# CAN-INTERFACES.net
KiCad netlist of a schematic drawn in Altium Designer
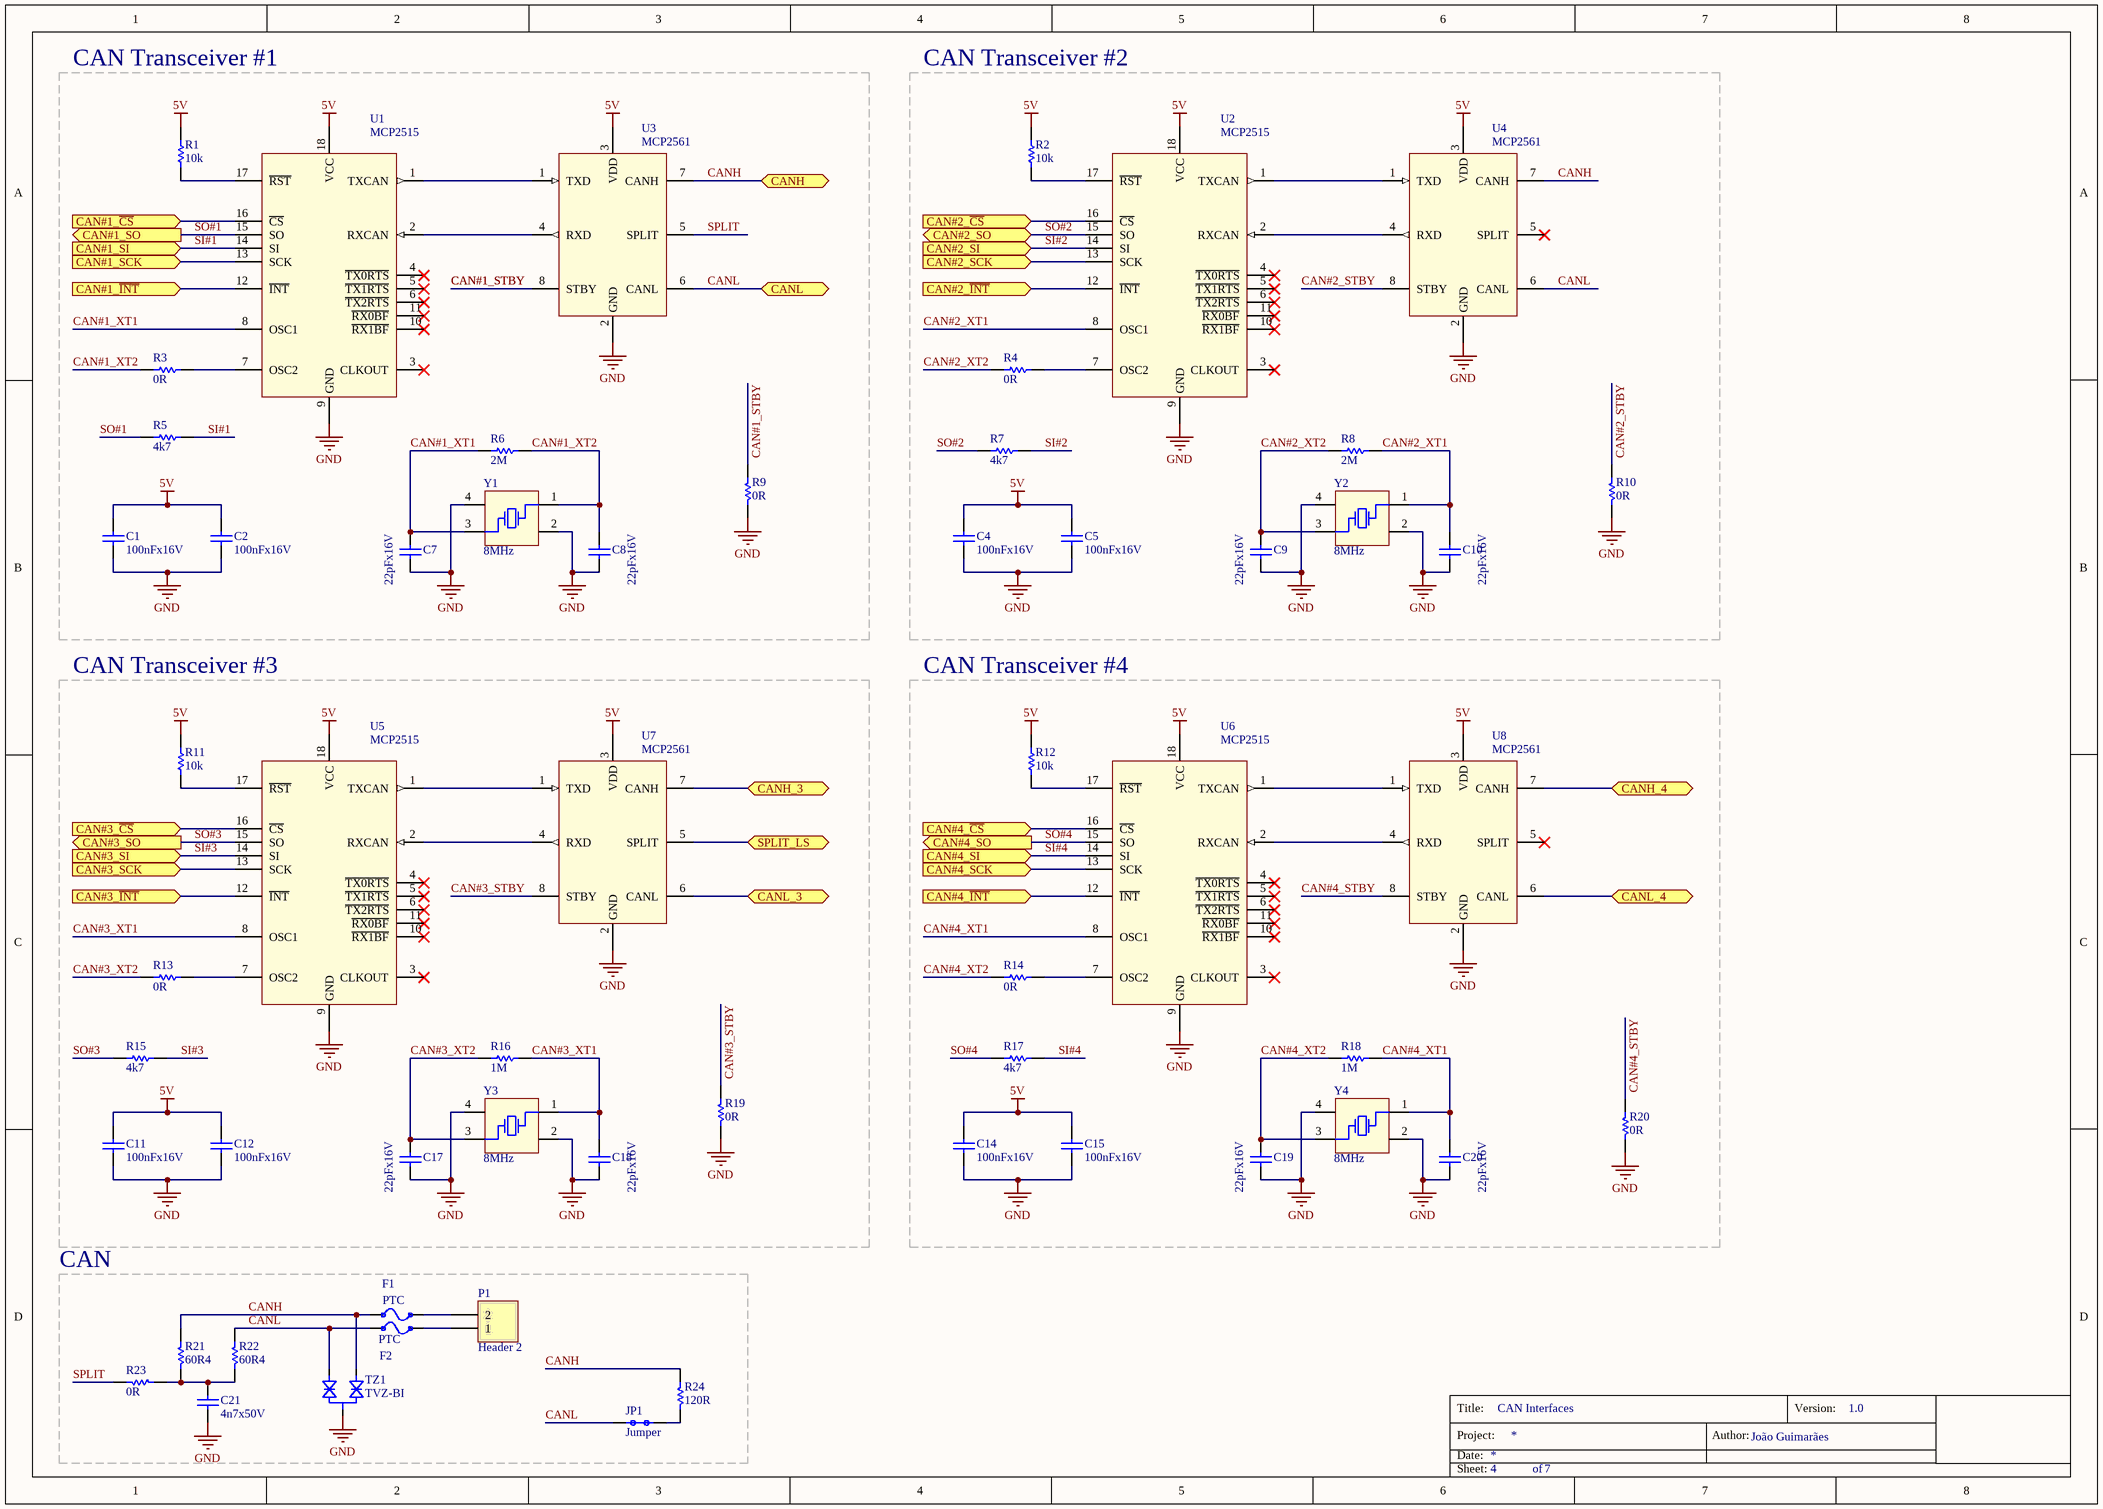
[diagram p0: CAN-INTERFACES.SchDoc]

(export (version "E")
  (design (tool "Eeschema 10.0.6"))
  (components
    (comp (ref "C1")
      (value "100nFx16V")
      (footprint "DISC-0603")
      (description "Capacitor")
      (libsource (lib "IntLib") (part "Cap"))
    )
    (comp (ref "C2")
      (value "100nFx16V")
      (footprint "DISC-0603")
      (description "Capacitor")
      (libsource (lib "IntLib") (part "Cap"))
    )
    (comp (ref "C4")
      (value "100nFx16V")
      (footprint "DISC-0603")
      (description "Capacitor")
      (libsource (lib "IntLib") (part "Cap"))
    )
    (comp (ref "C5")
      (value "100nFx16V")
      (footprint "DISC-0603")
      (description "Capacitor")
      (libsource (lib "IntLib") (part "Cap"))
    )
    (comp (ref "C7")
      (value "22pFx16V")
      (footprint "DISC-0603")
      (description "Capacitor")
      (libsource (lib "IntLib") (part "Cap"))
    )
    (comp (ref "C8")
      (value "22pFx16V")
      (footprint "DISC-0603")
      (description "Capacitor")
      (libsource (lib "IntLib") (part "Cap"))
    )
    (comp (ref "C9")
      (value "22pFx16V")
      (footprint "DISC-0603")
      (description "Capacitor")
      (libsource (lib "IntLib") (part "Cap"))
    )
    (comp (ref "C10")
      (value "22pFx16V")
      (footprint "DISC-0603")
      (description "Capacitor")
      (libsource (lib "IntLib") (part "Cap"))
    )
    (comp (ref "C11")
      (value "100nFx16V")
      (footprint "DISC-0603")
      (description "Capacitor")
      (libsource (lib "IntLib") (part "Cap"))
    )
    (comp (ref "C12")
      (value "100nFx16V")
      (footprint "DISC-0603")
      (description "Capacitor")
      (libsource (lib "IntLib") (part "Cap"))
    )
    (comp (ref "C14")
      (value "100nFx16V")
      (footprint "DISC-0603")
      (description "Capacitor")
      (libsource (lib "IntLib") (part "Cap"))
    )
    (comp (ref "C15")
      (value "100nFx16V")
      (footprint "DISC-0603")
      (description "Capacitor")
      (libsource (lib "IntLib") (part "Cap"))
    )
    (comp (ref "C17")
      (value "22pFx16V")
      (footprint "DISC-0603")
      (description "Capacitor")
      (libsource (lib "IntLib") (part "Cap"))
    )
    (comp (ref "C18")
      (value "22pFx16V")
      (footprint "DISC-0603")
      (description "Capacitor")
      (libsource (lib "IntLib") (part "Cap"))
    )
    (comp (ref "C19")
      (value "22pFx16V")
      (footprint "DISC-0603")
      (description "Capacitor")
      (libsource (lib "IntLib") (part "Cap"))
    )
    (comp (ref "C20")
      (value "22pFx16V")
      (footprint "DISC-0603")
      (description "Capacitor")
      (libsource (lib "IntLib") (part "Cap"))
    )
    (comp (ref "C21")
      (value "4n7x50V")
      (footprint "DISC-0603")
      (description "Capacitor")
      (libsource (lib "IntLib") (part "Cap"))
    )
    (comp (ref "F1")
      (value "PTC")
      (footprint "DISC-FUSE-1206")
      (description "Fuse")
      (fields (field (name "PUBLISHER") "Altium Limited"))
      (libsource (lib "IntLib") (part "Fuse 2"))
    )
    (comp (ref "F2")
      (value "PTC")
      (footprint "DISC-FUSE-1206")
      (description "Fuse")
      (fields (field (name "PUBLISHER") "Altium Limited"))
      (libsource (lib "IntLib") (part "Fuse 2"))
    )
    (comp (ref "JP1")
      (value "Jumper")
      (footprint "CON-HEADER-1X2-PTH")
      (description "Resistor")
      (libsource (lib "IntLib") (part "Jumper"))
    )
    (comp (ref "P1")
      (value "Header 2")
      (footprint "CON-BORNE-2")
      (description "Header, 2-Pin")
      (fields (field (name "PUBLISHER") "Altium Limited"))
      (libsource (lib "IntLib") (part "Header 2"))
    )
    (comp (ref "R1")
      (value "10k")
      (footprint "DISC-0603")
      (description "Resistor")
      (libsource (lib "IntLib") (part "Res"))
    )
    (comp (ref "R2")
      (value "10k")
      (footprint "DISC-0603")
      (description "Resistor")
      (libsource (lib "IntLib") (part "Res"))
    )
    (comp (ref "R3")
      (value "0R")
      (footprint "DISC-0603")
      (description "Resistor")
      (libsource (lib "IntLib") (part "Res"))
    )
    (comp (ref "R4")
      (value "0R")
      (footprint "DISC-0603")
      (description "Resistor")
      (libsource (lib "IntLib") (part "Res"))
    )
    (comp (ref "R5")
      (value "4k7")
      (footprint "DISC-0603")
      (description "Resistor")
      (libsource (lib "IntLib") (part "Res"))
    )
    (comp (ref "R6")
      (value "2M")
      (footprint "DISC-0603")
      (description "Resistor")
      (libsource (lib "IntLib") (part "Res"))
    )
    (comp (ref "R7")
      (value "4k7")
      (footprint "DISC-0603")
      (description "Resistor")
      (libsource (lib "IntLib") (part "Res"))
    )
    (comp (ref "R8")
      (value "2M")
      (footprint "DISC-0603")
      (description "Resistor")
      (libsource (lib "IntLib") (part "Res"))
    )
    (comp (ref "R9")
      (value "0R")
      (footprint "DISC-0603")
      (description "Resistor")
      (libsource (lib "IntLib") (part "Res"))
    )
    (comp (ref "R10")
      (value "0R")
      (footprint "DISC-0603")
      (description "Resistor")
      (libsource (lib "IntLib") (part "Res"))
    )
    (comp (ref "R11")
      (value "10k")
      (footprint "DISC-0603")
      (description "Resistor")
      (libsource (lib "IntLib") (part "Res"))
    )
    (comp (ref "R12")
      (value "10k")
      (footprint "DISC-0603")
      (description "Resistor")
      (libsource (lib "IntLib") (part "Res"))
    )
    (comp (ref "R13")
      (value "0R")
      (footprint "DISC-0603")
      (description "Resistor")
      (libsource (lib "IntLib") (part "Res"))
    )
    (comp (ref "R14")
      (value "0R")
      (footprint "DISC-0603")
      (description "Resistor")
      (libsource (lib "IntLib") (part "Res"))
    )
    (comp (ref "R15")
      (value "4k7")
      (footprint "DISC-0603")
      (description "Resistor")
      (libsource (lib "IntLib") (part "Res"))
    )
    (comp (ref "R16")
      (value "1M")
      (footprint "DISC-0603")
      (description "Resistor")
      (libsource (lib "IntLib") (part "Res"))
    )
    (comp (ref "R17")
      (value "4k7")
      (footprint "DISC-0603")
      (description "Resistor")
      (libsource (lib "IntLib") (part "Res"))
    )
    (comp (ref "R18")
      (value "1M")
      (footprint "DISC-0603")
      (description "Resistor")
      (libsource (lib "IntLib") (part "Res"))
    )
    (comp (ref "R19")
      (value "0R")
      (footprint "DISC-0603")
      (description "Resistor")
      (libsource (lib "IntLib") (part "Res"))
    )
    (comp (ref "R20")
      (value "0R")
      (footprint "DISC-0603")
      (description "Resistor")
      (libsource (lib "IntLib") (part "Res"))
    )
    (comp (ref "R21") (value "60R4") (footprint "DISC-0805") (libsource (lib "IntLib") (part "Res")))
    (comp (ref "R22") (value "60R4") (footprint "DISC-0805") (libsource (lib "IntLib") (part "Res")))
    (comp (ref "R23")
      (value "0R")
      (footprint "DISC-0603")
      (description "Resistor")
      (libsource (lib "IntLib") (part "Res"))
    )
    (comp (ref "R24")
      (value "120R")
      (footprint "DISC-0805")
      (description "60R4")
      (libsource (lib "IntLib") (part "Res"))
    )
    (comp (ref "TZ1")
      (value "TVZ-BI")
      (footprint "DISC-SOT-23")
      (description "TVZ-Bi-Directional")
      (libsource (lib "IntLib") (part "TVZ-Bi-Dual"))
    )
    (comp (ref "U1")
      (value "MCP2515")
      (footprint "CI-SOICW-18")
      (description "Stand-Alone CAN Controller With SPI Interface")
      (libsource (lib "IntLib") (part "MCP2515"))
    )
    (comp (ref "U2")
      (value "MCP2515")
      (footprint "CI-SOICW-18")
      (description "Stand-Alone CAN Controller With SPI Interface")
      (libsource (lib "IntLib") (part "MCP2515"))
    )
    (comp (ref "U3")
      (value "MCP2561")
      (footprint "CI-SOIC-8")
      (description "High speed CAN transceiver")
      (libsource (lib "IntLib") (part "MCP2561"))
    )
    (comp (ref "U4")
      (value "MCP2561")
      (footprint "CI-SOIC-8")
      (description "High speed CAN transceiver")
      (libsource (lib "IntLib") (part "MCP2561"))
    )
    (comp (ref "U5")
      (value "MCP2515")
      (footprint "CI-SOICW-18")
      (description "Stand-Alone CAN Controller With SPI Interface")
      (libsource (lib "IntLib") (part "MCP2515"))
    )
    (comp (ref "U6")
      (value "MCP2515")
      (footprint "CI-SOICW-18")
      (description "Stand-Alone CAN Controller With SPI Interface")
      (libsource (lib "IntLib") (part "MCP2515"))
    )
    (comp (ref "U7")
      (value "MCP2561")
      (footprint "CI-SOIC-8")
      (description "High speed CAN transceiver")
      (libsource (lib "IntLib") (part "MCP2561"))
    )
    (comp (ref "U8")
      (value "MCP2561")
      (footprint "CI-SOIC-8")
      (description "High speed CAN transceiver")
      (libsource (lib "IntLib") (part "MCP2561"))
    )
    (comp (ref "Y1")
      (value "8MHz")
      (footprint "DISC-CRYSTAL-4P-3.2X2.5")
      (description "XTAL-4-PIN")
      (libsource (lib "IntLib") (part "XTAL-4-PIN"))
    )
    (comp (ref "Y2")
      (value "8MHz")
      (footprint "DISC-CRYSTAL-4P-3.2X2.5")
      (description "XTAL-4-PIN")
      (libsource (lib "IntLib") (part "XTAL-4-PIN"))
    )
    (comp (ref "Y3")
      (value "8MHz")
      (footprint "DISC-CRYSTAL-4P-3.2X2.5")
      (description "XTAL-4-PIN")
      (libsource (lib "IntLib") (part "XTAL-4-PIN"))
    )
    (comp (ref "Y4")
      (value "8MHz")
      (footprint "DISC-CRYSTAL-4P-3.2X2.5")
      (description "XTAL-4-PIN")
      (libsource (lib "IntLib") (part "XTAL-4-PIN"))
    )
  )
  (nets
    (net (code "1") (name "/CAN#1_SCK") (class "Default")
      (node (ref "U1") (pin "13") (pinfunction "SCK_13") (pintype "passive"))
    )
    (net (code "2") (name "/CAN#1_STBY") (class "Default")
      (node (ref "R9") (pin "2") (pinfunction "2_2") (pintype "passive"))
      (node (ref "U3") (pin "8") (pinfunction "STBY_8") (pintype "passive"))
    )
    (net (code "3") (name "/CAN#1_XT1") (class "Default")
      (node (ref "C7") (pin "2") (pinfunction "2_2") (pintype "passive"))
      (node (ref "R6") (pin "1") (pinfunction "1_1") (pintype "passive"))
      (node (ref "U1") (pin "8") (pinfunction "OSC1_8") (pintype "passive"))
      (node (ref "Y1") (pin "3") (pinfunction "OSC2_3") (pintype "passive"))
    )
    (net (code "4") (name "/CAN#1_XT2") (class "Default")
      (node (ref "C8") (pin "2") (pinfunction "2_2") (pintype "passive"))
      (node (ref "R3") (pin "2") (pinfunction "2_2") (pintype "passive"))
      (node (ref "R6") (pin "2") (pinfunction "2_2") (pintype "passive"))
      (node (ref "Y1") (pin "1") (pinfunction "OSC1_1") (pintype "passive"))
    )
    (net (code "5") (name "/CAN#1_~{CS}") (class "Default")
      (node (ref "U1") (pin "16") (pinfunction "~{CS}_16") (pintype "passive"))
    )
    (net (code "6") (name "/CAN#1_~{INT}") (class "Default")
      (node (ref "U1") (pin "12") (pinfunction "~{INT}_12") (pintype "passive"))
    )
    (net (code "7") (name "/CAN#2_SCK") (class "Default")
      (node (ref "U2") (pin "13") (pinfunction "SCK_13") (pintype "passive"))
    )
    (net (code "8") (name "/CAN#2_STBY") (class "Default")
      (node (ref "R10") (pin "2") (pinfunction "2_2") (pintype "passive"))
      (node (ref "U4") (pin "8") (pinfunction "STBY_8") (pintype "passive"))
    )
    (net (code "9") (name "/CAN#2_XT1") (class "Default")
      (node (ref "C10") (pin "2") (pinfunction "2_2") (pintype "passive"))
      (node (ref "R8") (pin "2") (pinfunction "2_2") (pintype "passive"))
      (node (ref "U2") (pin "8") (pinfunction "OSC1_8") (pintype "passive"))
      (node (ref "Y2") (pin "1") (pinfunction "OSC1_1") (pintype "passive"))
    )
    (net (code "10") (name "/CAN#2_XT2") (class "Default")
      (node (ref "C9") (pin "2") (pinfunction "2_2") (pintype "passive"))
      (node (ref "R4") (pin "2") (pinfunction "2_2") (pintype "passive"))
      (node (ref "R8") (pin "1") (pinfunction "1_1") (pintype "passive"))
      (node (ref "Y2") (pin "3") (pinfunction "OSC2_3") (pintype "passive"))
    )
    (net (code "11") (name "/CAN#2_~{CS}") (class "Default")
      (node (ref "U2") (pin "16") (pinfunction "~{CS}_16") (pintype "passive"))
    )
    (net (code "12") (name "/CAN#2_~{INT}") (class "Default")
      (node (ref "U2") (pin "12") (pinfunction "~{INT}_12") (pintype "passive"))
    )
    (net (code "13") (name "/CAN#3_SCK") (class "Default")
      (node (ref "U5") (pin "13") (pinfunction "SCK_13") (pintype "passive"))
    )
    (net (code "14") (name "/CAN#3_STBY") (class "Default")
      (node (ref "R19") (pin "2") (pinfunction "2_2") (pintype "passive"))
      (node (ref "U7") (pin "8") (pinfunction "STBY_8") (pintype "passive"))
    )
    (net (code "15") (name "/CAN#3_XT1") (class "Default")
      (node (ref "C18") (pin "2") (pinfunction "2_2") (pintype "passive"))
      (node (ref "R16") (pin "2") (pinfunction "2_2") (pintype "passive"))
      (node (ref "U5") (pin "8") (pinfunction "OSC1_8") (pintype "passive"))
      (node (ref "Y3") (pin "1") (pinfunction "OSC1_1") (pintype "passive"))
    )
    (net (code "16") (name "/CAN#3_XT2") (class "Default")
      (node (ref "C17") (pin "2") (pinfunction "2_2") (pintype "passive"))
      (node (ref "R13") (pin "2") (pinfunction "2_2") (pintype "passive"))
      (node (ref "R16") (pin "1") (pinfunction "1_1") (pintype "passive"))
      (node (ref "Y3") (pin "3") (pinfunction "OSC2_3") (pintype "passive"))
    )
    (net (code "17") (name "/CAN#3_~{CS}") (class "Default")
      (node (ref "U5") (pin "16") (pinfunction "~{CS}_16") (pintype "passive"))
    )
    (net (code "18") (name "/CAN#3_~{INT}") (class "Default")
      (node (ref "U5") (pin "12") (pinfunction "~{INT}_12") (pintype "passive"))
    )
    (net (code "19") (name "/CAN#4_SCK") (class "Default")
      (node (ref "U6") (pin "13") (pinfunction "SCK_13") (pintype "passive"))
    )
    (net (code "20") (name "/CAN#4_STBY") (class "Default")
      (node (ref "R20") (pin "2") (pinfunction "2_2") (pintype "passive"))
      (node (ref "U8") (pin "8") (pinfunction "STBY_8") (pintype "passive"))
    )
    (net (code "21") (name "/CAN#4_XT1") (class "Default")
      (node (ref "C20") (pin "2") (pinfunction "2_2") (pintype "passive"))
      (node (ref "R18") (pin "2") (pinfunction "2_2") (pintype "passive"))
      (node (ref "U6") (pin "8") (pinfunction "OSC1_8") (pintype "passive"))
      (node (ref "Y4") (pin "1") (pinfunction "OSC1_1") (pintype "passive"))
    )
    (net (code "22") (name "/CAN#4_XT2") (class "Default")
      (node (ref "C19") (pin "2") (pinfunction "2_2") (pintype "passive"))
      (node (ref "R14") (pin "2") (pinfunction "2_2") (pintype "passive"))
      (node (ref "R18") (pin "1") (pinfunction "1_1") (pintype "passive"))
      (node (ref "Y4") (pin "3") (pinfunction "OSC2_3") (pintype "passive"))
    )
    (net (code "23") (name "/CAN#4_~{CS}") (class "Default")
      (node (ref "U6") (pin "16") (pinfunction "~{CS}_16") (pintype "passive"))
    )
    (net (code "24") (name "/CAN#4_~{INT}") (class "Default")
      (node (ref "U6") (pin "12") (pinfunction "~{INT}_12") (pintype "passive"))
    )
    (net (code "25") (name "/CANH") (class "Default")
      (node (ref "F1") (pin "1") (pinfunction "1_1") (pintype "passive"))
      (node (ref "R21") (pin "2") (pinfunction "2_2") (pintype "passive"))
      (node (ref "R24") (pin "1") (pinfunction "1_1") (pintype "passive"))
      (node (ref "TZ1") (pin "3") (pinfunction "A2_3") (pintype "passive"))
      (node (ref "U3") (pin "7") (pinfunction "CANH_7") (pintype "passive"))
      (node (ref "U4") (pin "7") (pinfunction "CANH_7") (pintype "passive"))
    )
    (net (code "26") (name "/CANH_3") (class "Default")
      (node (ref "U7") (pin "7") (pinfunction "CANH_7") (pintype "passive"))
    )
    (net (code "27") (name "/CANH_4") (class "Default")
      (node (ref "U8") (pin "7") (pinfunction "CANH_7") (pintype "passive"))
    )
    (net (code "28") (name "/CANL") (class "Default")
      (node (ref "F2") (pin "1") (pinfunction "1_1") (pintype "passive"))
      (node (ref "JP1") (pin "1") (pinfunction "1_1") (pintype "passive"))
      (node (ref "R22") (pin "2") (pinfunction "2_2") (pintype "passive"))
      (node (ref "TZ1") (pin "1") (pinfunction "A1_1") (pintype "passive"))
      (node (ref "U3") (pin "6") (pinfunction "CANL_6") (pintype "passive"))
      (node (ref "U4") (pin "6") (pinfunction "CANL_6") (pintype "passive"))
    )
    (net (code "29") (name "/CANL_3") (class "Default")
      (node (ref "U7") (pin "6") (pinfunction "CANL_6") (pintype "passive"))
    )
    (net (code "30") (name "/CANL_4") (class "Default")
      (node (ref "U8") (pin "6") (pinfunction "CANL_6") (pintype "passive"))
    )
    (net (code "31") (name "/SI#1") (class "Default")
      (node (ref "R5") (pin "1") (pinfunction "1_1") (pintype "passive"))
      (node (ref "U1") (pin "14") (pinfunction "SI_14") (pintype "passive"))
    )
    (net (code "32") (name "/SI#2") (class "Default")
      (node (ref "R7") (pin "1") (pinfunction "1_1") (pintype "passive"))
      (node (ref "U2") (pin "14") (pinfunction "SI_14") (pintype "passive"))
    )
    (net (code "33") (name "/SI#3") (class "Default")
      (node (ref "R15") (pin "1") (pinfunction "1_1") (pintype "passive"))
      (node (ref "U5") (pin "14") (pinfunction "SI_14") (pintype "passive"))
    )
    (net (code "34") (name "/SI#4") (class "Default")
      (node (ref "R17") (pin "1") (pinfunction "1_1") (pintype "passive"))
      (node (ref "U6") (pin "14") (pinfunction "SI_14") (pintype "passive"))
    )
    (net (code "35") (name "/SO#1") (class "Default")
      (node (ref "R5") (pin "2") (pinfunction "2_2") (pintype "passive"))
      (node (ref "U1") (pin "15") (pinfunction "SO_15") (pintype "passive"))
    )
    (net (code "36") (name "/SO#2") (class "Default")
      (node (ref "R7") (pin "2") (pinfunction "2_2") (pintype "passive"))
      (node (ref "U2") (pin "15") (pinfunction "SO_15") (pintype "passive"))
    )
    (net (code "37") (name "/SO#3") (class "Default")
      (node (ref "R15") (pin "2") (pinfunction "2_2") (pintype "passive"))
      (node (ref "U5") (pin "15") (pinfunction "SO_15") (pintype "passive"))
    )
    (net (code "38") (name "/SO#4") (class "Default")
      (node (ref "R17") (pin "2") (pinfunction "2_2") (pintype "passive"))
      (node (ref "U6") (pin "15") (pinfunction "SO_15") (pintype "passive"))
    )
    (net (code "39") (name "/SPLIT") (class "Default")
      (node (ref "R23") (pin "1") (pinfunction "1_1") (pintype "passive"))
      (node (ref "U3") (pin "5") (pinfunction "SPLIT_5") (pintype "passive"))
    )
    (net (code "40") (name "/SPLIT_LS") (class "Default")
      (node (ref "U7") (pin "5") (pinfunction "SPLIT_5") (pintype "passive"))
    )
    (net (code "41") (name "5V") (class "Default")
      (node (ref "C1") (pin "1") (pinfunction "1_1") (pintype "passive"))
      (node (ref "C11") (pin "1") (pinfunction "1_1") (pintype "passive"))
      (node (ref "C12") (pin "1") (pinfunction "1_1") (pintype "passive"))
      (node (ref "C14") (pin "1") (pinfunction "1_1") (pintype "passive"))
      (node (ref "C15") (pin "1") (pinfunction "1_1") (pintype "passive"))
      (node (ref "C2") (pin "1") (pinfunction "1_1") (pintype "passive"))
      (node (ref "C4") (pin "1") (pinfunction "1_1") (pintype "passive"))
      (node (ref "C5") (pin "1") (pinfunction "1_1") (pintype "passive"))
      (node (ref "R1") (pin "1") (pinfunction "1_1") (pintype "passive"))
      (node (ref "R11") (pin "1") (pinfunction "1_1") (pintype "passive"))
      (node (ref "R12") (pin "1") (pinfunction "1_1") (pintype "passive"))
      (node (ref "R2") (pin "1") (pinfunction "1_1") (pintype "passive"))
      (node (ref "U1") (pin "18") (pinfunction "VCC_18") (pintype "power_in"))
      (node (ref "U2") (pin "18") (pinfunction "VCC_18") (pintype "power_in"))
      (node (ref "U3") (pin "3") (pinfunction "VDD_3") (pintype "power_in"))
      (node (ref "U4") (pin "3") (pinfunction "VDD_3") (pintype "power_in"))
      (node (ref "U5") (pin "18") (pinfunction "VCC_18") (pintype "power_in"))
      (node (ref "U6") (pin "18") (pinfunction "VCC_18") (pintype "power_in"))
      (node (ref "U7") (pin "3") (pinfunction "VDD_3") (pintype "power_in"))
      (node (ref "U8") (pin "3") (pinfunction "VDD_3") (pintype "power_in"))
    )
    (net (code "42") (name "GND") (class "Default")
      (node (ref "C1") (pin "2") (pinfunction "2_2") (pintype "passive"))
      (node (ref "C10") (pin "1") (pinfunction "1_1") (pintype "passive"))
      (node (ref "C11") (pin "2") (pinfunction "2_2") (pintype "passive"))
      (node (ref "C12") (pin "2") (pinfunction "2_2") (pintype "passive"))
      (node (ref "C14") (pin "2") (pinfunction "2_2") (pintype "passive"))
      (node (ref "C15") (pin "2") (pinfunction "2_2") (pintype "passive"))
      (node (ref "C17") (pin "1") (pinfunction "1_1") (pintype "passive"))
      (node (ref "C18") (pin "1") (pinfunction "1_1") (pintype "passive"))
      (node (ref "C19") (pin "1") (pinfunction "1_1") (pintype "passive"))
      (node (ref "C2") (pin "2") (pinfunction "2_2") (pintype "passive"))
      (node (ref "C20") (pin "1") (pinfunction "1_1") (pintype "passive"))
      (node (ref "C21") (pin "1") (pinfunction "1_1") (pintype "passive"))
      (node (ref "C4") (pin "2") (pinfunction "2_2") (pintype "passive"))
      (node (ref "C5") (pin "2") (pinfunction "2_2") (pintype "passive"))
      (node (ref "C7") (pin "1") (pinfunction "1_1") (pintype "passive"))
      (node (ref "C8") (pin "1") (pinfunction "1_1") (pintype "passive"))
      (node (ref "C9") (pin "1") (pinfunction "1_1") (pintype "passive"))
      (node (ref "R10") (pin "1") (pinfunction "1_1") (pintype "passive"))
      (node (ref "R19") (pin "1") (pinfunction "1_1") (pintype "passive"))
      (node (ref "R20") (pin "1") (pinfunction "1_1") (pintype "passive"))
      (node (ref "R9") (pin "1") (pinfunction "1_1") (pintype "passive"))
      (node (ref "TZ1") (pin "2") (pinfunction "K_2") (pintype "passive"))
      (node (ref "U1") (pin "9") (pinfunction "GND_9") (pintype "power_in"))
      (node (ref "U2") (pin "9") (pinfunction "GND_9") (pintype "power_in"))
      (node (ref "U3") (pin "2") (pinfunction "GND_2") (pintype "power_in"))
      (node (ref "U4") (pin "2") (pinfunction "GND_2") (pintype "power_in"))
      (node (ref "U5") (pin "9") (pinfunction "GND_9") (pintype "power_in"))
      (node (ref "U6") (pin "9") (pinfunction "GND_9") (pintype "power_in"))
      (node (ref "U7") (pin "2") (pinfunction "GND_2") (pintype "power_in"))
      (node (ref "U8") (pin "2") (pinfunction "GND_2") (pintype "power_in"))
      (node (ref "Y1") (pin "2") (pinfunction "GND_2") (pintype "passive"))
      (node (ref "Y1") (pin "4") (pinfunction "GND_4") (pintype "passive"))
      (node (ref "Y2") (pin "2") (pinfunction "GND_2") (pintype "passive"))
      (node (ref "Y2") (pin "4") (pinfunction "GND_4") (pintype "passive"))
      (node (ref "Y3") (pin "2") (pinfunction "GND_2") (pintype "passive"))
      (node (ref "Y3") (pin "4") (pinfunction "GND_4") (pintype "passive"))
      (node (ref "Y4") (pin "2") (pinfunction "GND_2") (pintype "passive"))
      (node (ref "Y4") (pin "4") (pinfunction "GND_4") (pintype "passive"))
    )
    (net (code "43") (name "Net-(C21-Pad2)") (class "Default")
      (node (ref "C21") (pin "2") (pinfunction "2_2") (pintype "passive"))
      (node (ref "R21") (pin "1") (pinfunction "1_1") (pintype "passive"))
      (node (ref "R22") (pin "1") (pinfunction "1_1") (pintype "passive"))
      (node (ref "R23") (pin "2") (pinfunction "2_2") (pintype "passive"))
    )
    (net (code "44") (name "Net-(F1-Pad2)") (class "Default")
      (node (ref "F1") (pin "2") (pinfunction "2_2") (pintype "passive"))
      (node (ref "P1") (pin "2") (pinfunction "2_2") (pintype "passive"))
    )
    (net (code "45") (name "Net-(F2-Pad2)") (class "Default")
      (node (ref "F2") (pin "2") (pinfunction "2_2") (pintype "passive"))
      (node (ref "P1") (pin "1") (pinfunction "1_1") (pintype "passive"))
    )
    (net (code "46") (name "Net-(JP1-Pad2)") (class "Default")
      (node (ref "JP1") (pin "2") (pinfunction "2_2") (pintype "passive"))
      (node (ref "R24") (pin "2") (pinfunction "2_2") (pintype "passive"))
    )
    (net (code "47") (name "Net-(U1-OSC2)") (class "Default")
      (node (ref "R3") (pin "1") (pinfunction "1_1") (pintype "passive"))
      (node (ref "U1") (pin "7") (pinfunction "OSC2_7") (pintype "passive"))
    )
    (net (code "48") (name "Net-(U1-RXCAN)") (class "Default")
      (node (ref "U1") (pin "2") (pinfunction "RXCAN_2") (pintype "input"))
      (node (ref "U3") (pin "4") (pinfunction "RXD_4") (pintype "output"))
    )
    (net (code "49") (name "Net-(U1-TXCAN)") (class "Default")
      (node (ref "U1") (pin "1") (pinfunction "TXCAN_1") (pintype "output"))
      (node (ref "U3") (pin "1") (pinfunction "TXD_1") (pintype "input"))
    )
    (net (code "50") (name "Net-(U1-~{RST})") (class "Default")
      (node (ref "R1") (pin "2") (pinfunction "2_2") (pintype "passive"))
      (node (ref "U1") (pin "17") (pinfunction "~{RST}_17") (pintype "passive"))
    )
    (net (code "51") (name "Net-(U2-OSC2)") (class "Default")
      (node (ref "R4") (pin "1") (pinfunction "1_1") (pintype "passive"))
      (node (ref "U2") (pin "7") (pinfunction "OSC2_7") (pintype "passive"))
    )
    (net (code "52") (name "Net-(U2-RXCAN)") (class "Default")
      (node (ref "U2") (pin "2") (pinfunction "RXCAN_2") (pintype "input"))
      (node (ref "U4") (pin "4") (pinfunction "RXD_4") (pintype "output"))
    )
    (net (code "53") (name "Net-(U2-TXCAN)") (class "Default")
      (node (ref "U2") (pin "1") (pinfunction "TXCAN_1") (pintype "output"))
      (node (ref "U4") (pin "1") (pinfunction "TXD_1") (pintype "input"))
    )
    (net (code "54") (name "Net-(U2-~{RST})") (class "Default")
      (node (ref "R2") (pin "2") (pinfunction "2_2") (pintype "passive"))
      (node (ref "U2") (pin "17") (pinfunction "~{RST}_17") (pintype "passive"))
    )
    (net (code "55") (name "Net-(U5-OSC2)") (class "Default")
      (node (ref "R13") (pin "1") (pinfunction "1_1") (pintype "passive"))
      (node (ref "U5") (pin "7") (pinfunction "OSC2_7") (pintype "passive"))
    )
    (net (code "56") (name "Net-(U5-RXCAN)") (class "Default")
      (node (ref "U5") (pin "2") (pinfunction "RXCAN_2") (pintype "input"))
      (node (ref "U7") (pin "4") (pinfunction "RXD_4") (pintype "output"))
    )
    (net (code "57") (name "Net-(U5-TXCAN)") (class "Default")
      (node (ref "U5") (pin "1") (pinfunction "TXCAN_1") (pintype "output"))
      (node (ref "U7") (pin "1") (pinfunction "TXD_1") (pintype "input"))
    )
    (net (code "58") (name "Net-(U5-~{RST})") (class "Default")
      (node (ref "R11") (pin "2") (pinfunction "2_2") (pintype "passive"))
      (node (ref "U5") (pin "17") (pinfunction "~{RST}_17") (pintype "passive"))
    )
    (net (code "59") (name "Net-(U6-OSC2)") (class "Default")
      (node (ref "R14") (pin "1") (pinfunction "1_1") (pintype "passive"))
      (node (ref "U6") (pin "7") (pinfunction "OSC2_7") (pintype "passive"))
    )
    (net (code "60") (name "Net-(U6-RXCAN)") (class "Default")
      (node (ref "U6") (pin "2") (pinfunction "RXCAN_2") (pintype "input"))
      (node (ref "U8") (pin "4") (pinfunction "RXD_4") (pintype "output"))
    )
    (net (code "61") (name "Net-(U6-TXCAN)") (class "Default")
      (node (ref "U6") (pin "1") (pinfunction "TXCAN_1") (pintype "output"))
      (node (ref "U8") (pin "1") (pinfunction "TXD_1") (pintype "input"))
    )
    (net (code "62") (name "Net-(U6-~{RST})") (class "Default")
      (node (ref "R12") (pin "2") (pinfunction "2_2") (pintype "passive"))
      (node (ref "U6") (pin "17") (pinfunction "~{RST}_17") (pintype "passive"))
    )
    (net (code "63") (name "unconnected-(U1-CLKOUT-Pad3)") (class "Default")
      (node (ref "U1") (pin "3") (pinfunction "CLKOUT_3") (pintype "passive+no_connect"))
    )
    (net (code "64") (name "unconnected-(U1-~{RX0BF}-Pad11)") (class "Default")
      (node (ref "U1") (pin "11") (pinfunction "~{RX0BF}_11") (pintype "passive+no_connect"))
    )
    (net (code "65") (name "unconnected-(U1-~{RX1BF}-Pad10)") (class "Default")
      (node (ref "U1") (pin "10") (pinfunction "~{RX1BF}_10") (pintype "passive+no_connect"))
    )
    (net (code "66") (name "unconnected-(U1-~{TX0RTS}-Pad4)") (class "Default")
      (node (ref "U1") (pin "4") (pinfunction "~{TX0RTS}_4") (pintype "passive+no_connect"))
    )
    (net (code "67") (name "unconnected-(U1-~{TX1RTS}-Pad5)") (class "Default")
      (node (ref "U1") (pin "5") (pinfunction "~{TX1RTS}_5") (pintype "passive+no_connect"))
    )
    (net (code "68") (name "unconnected-(U1-~{TX2RTS}-Pad6)") (class "Default")
      (node (ref "U1") (pin "6") (pinfunction "~{TX2RTS}_6") (pintype "passive+no_connect"))
    )
    (net (code "69") (name "unconnected-(U2-CLKOUT-Pad3)") (class "Default")
      (node (ref "U2") (pin "3") (pinfunction "CLKOUT_3") (pintype "passive+no_connect"))
    )
    (net (code "70") (name "unconnected-(U2-~{RX0BF}-Pad11)") (class "Default")
      (node (ref "U2") (pin "11") (pinfunction "~{RX0BF}_11") (pintype "passive+no_connect"))
    )
    (net (code "71") (name "unconnected-(U2-~{RX1BF}-Pad10)") (class "Default")
      (node (ref "U2") (pin "10") (pinfunction "~{RX1BF}_10") (pintype "passive+no_connect"))
    )
    (net (code "72") (name "unconnected-(U2-~{TX0RTS}-Pad4)") (class "Default")
      (node (ref "U2") (pin "4") (pinfunction "~{TX0RTS}_4") (pintype "passive+no_connect"))
    )
    (net (code "73") (name "unconnected-(U2-~{TX1RTS}-Pad5)") (class "Default")
      (node (ref "U2") (pin "5") (pinfunction "~{TX1RTS}_5") (pintype "passive+no_connect"))
    )
    (net (code "74") (name "unconnected-(U2-~{TX2RTS}-Pad6)") (class "Default")
      (node (ref "U2") (pin "6") (pinfunction "~{TX2RTS}_6") (pintype "passive+no_connect"))
    )
    (net (code "75") (name "unconnected-(U4-SPLIT-Pad5)") (class "Default")
      (node (ref "U4") (pin "5") (pinfunction "SPLIT_5") (pintype "passive+no_connect"))
    )
    (net (code "76") (name "unconnected-(U5-CLKOUT-Pad3)") (class "Default")
      (node (ref "U5") (pin "3") (pinfunction "CLKOUT_3") (pintype "passive+no_connect"))
    )
    (net (code "77") (name "unconnected-(U5-~{RX0BF}-Pad11)") (class "Default")
      (node (ref "U5") (pin "11") (pinfunction "~{RX0BF}_11") (pintype "passive+no_connect"))
    )
    (net (code "78") (name "unconnected-(U5-~{RX1BF}-Pad10)") (class "Default")
      (node (ref "U5") (pin "10") (pinfunction "~{RX1BF}_10") (pintype "passive+no_connect"))
    )
    (net (code "79") (name "unconnected-(U5-~{TX0RTS}-Pad4)") (class "Default")
      (node (ref "U5") (pin "4") (pinfunction "~{TX0RTS}_4") (pintype "passive+no_connect"))
    )
    (net (code "80") (name "unconnected-(U5-~{TX1RTS}-Pad5)") (class "Default")
      (node (ref "U5") (pin "5") (pinfunction "~{TX1RTS}_5") (pintype "passive+no_connect"))
    )
    (net (code "81") (name "unconnected-(U5-~{TX2RTS}-Pad6)") (class "Default")
      (node (ref "U5") (pin "6") (pinfunction "~{TX2RTS}_6") (pintype "passive+no_connect"))
    )
    (net (code "82") (name "unconnected-(U6-CLKOUT-Pad3)") (class "Default")
      (node (ref "U6") (pin "3") (pinfunction "CLKOUT_3") (pintype "passive+no_connect"))
    )
    (net (code "83") (name "unconnected-(U6-~{RX0BF}-Pad11)") (class "Default")
      (node (ref "U6") (pin "11") (pinfunction "~{RX0BF}_11") (pintype "passive+no_connect"))
    )
    (net (code "84") (name "unconnected-(U6-~{RX1BF}-Pad10)") (class "Default")
      (node (ref "U6") (pin "10") (pinfunction "~{RX1BF}_10") (pintype "passive+no_connect"))
    )
    (net (code "85") (name "unconnected-(U6-~{TX0RTS}-Pad4)") (class "Default")
      (node (ref "U6") (pin "4") (pinfunction "~{TX0RTS}_4") (pintype "passive+no_connect"))
    )
    (net (code "86") (name "unconnected-(U6-~{TX1RTS}-Pad5)") (class "Default")
      (node (ref "U6") (pin "5") (pinfunction "~{TX1RTS}_5") (pintype "passive+no_connect"))
    )
    (net (code "87") (name "unconnected-(U6-~{TX2RTS}-Pad6)") (class "Default")
      (node (ref "U6") (pin "6") (pinfunction "~{TX2RTS}_6") (pintype "passive+no_connect"))
    )
    (net (code "88") (name "unconnected-(U8-SPLIT-Pad5)") (class "Default")
      (node (ref "U8") (pin "5") (pinfunction "SPLIT_5") (pintype "passive+no_connect"))
    )
  )
)
